# Main.net
KiCad netlist of a schematic drawn in Altium Designer
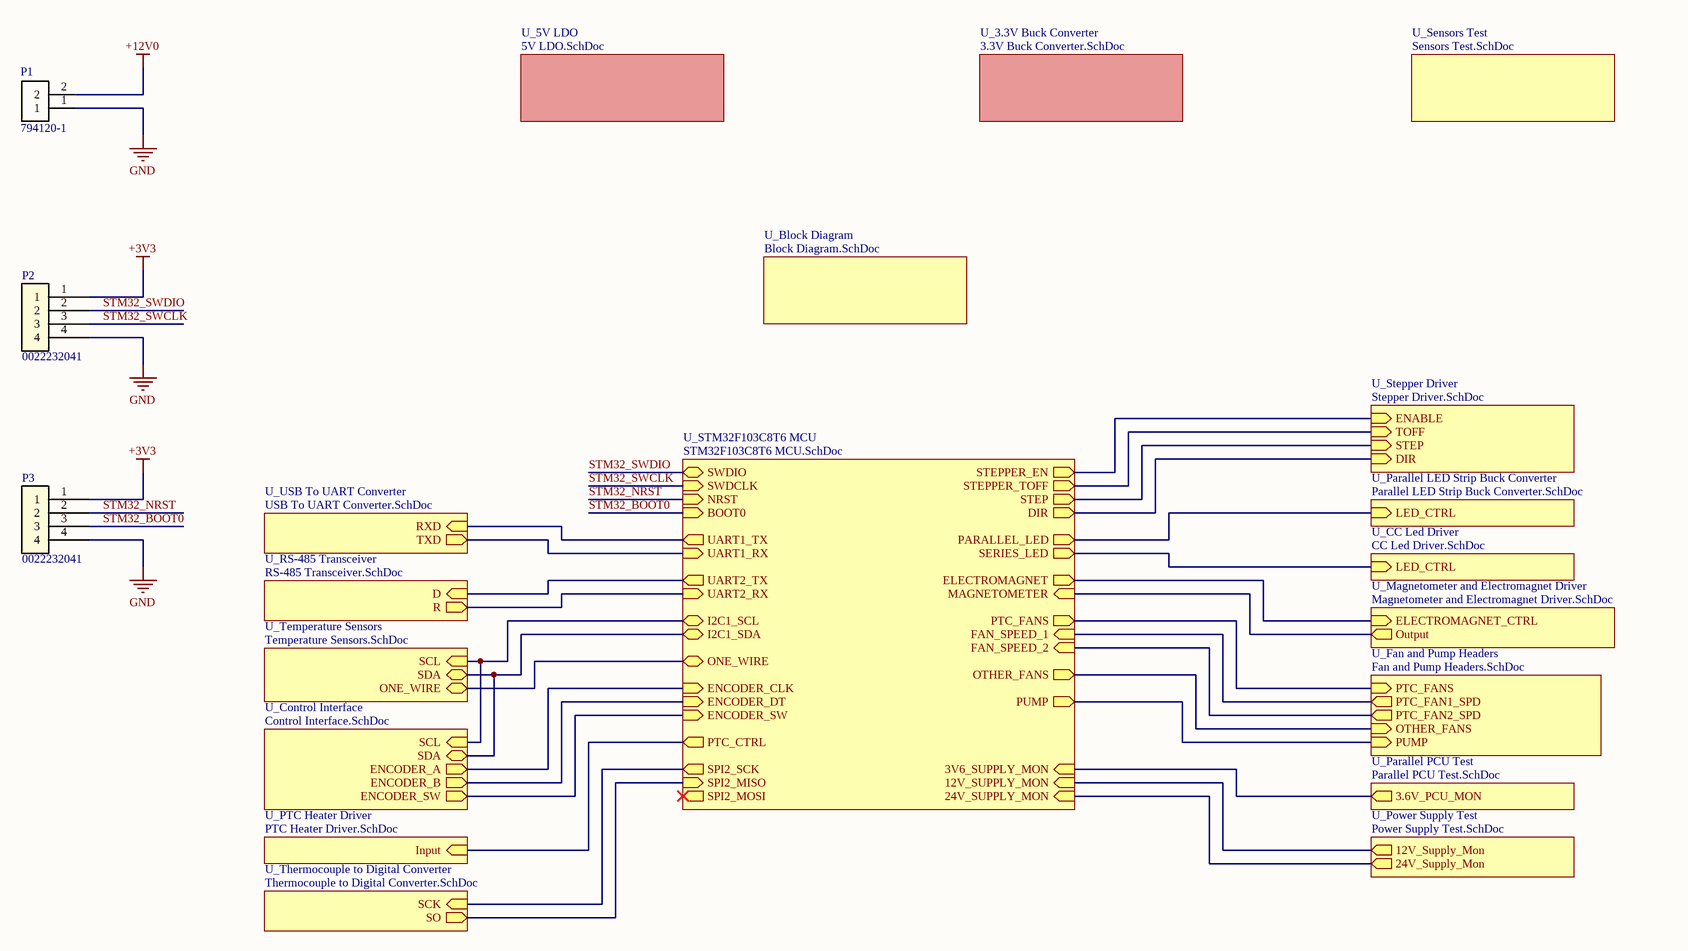
[diagram p0: Main.SchDoc]

(export (version "E")
  (design (tool "Eeschema 10.0.6"))
  (components
    (comp (ref "P1")
      (value "794120-1")
      (footprint "POWER2-5.08 right angle")
      (fields (field (name "MP") "TE Connectivity"))
      (libsource (lib "Connectors") (part "Power2"))
    )
    (comp (ref "P2")
      (value "0022232041")
      (footprint "Signal4")
      (description "SignalConnector, 4 leads")
      (fields (field (name "MF") "Molex"))
      (libsource (lib "Connectors") (part "Signal4"))
    )
    (comp (ref "P3")
      (value "0022232041")
      (footprint "Signal4")
      (description "SignalConnector, 4 leads")
      (fields (field (name "MF") "Molex"))
      (libsource (lib "Connectors") (part "Signal4"))
    )
  )
  (nets
    (net (code "1") (name "+3V3") (class "Default")
      (node (ref "P2") (pin "1") (pinfunction "1_1") (pintype "passive"))
      (node (ref "P3") (pin "1") (pinfunction "1_1") (pintype "passive"))
    )
    (net (code "2") (name "+12V0") (class "Default")
      (node (ref "P1") (pin "2") (pinfunction "2_2") (pintype "passive"))
    )
    (net (code "30") (name "/STM32_BOOT0") (class "Default")
      (node (ref "P3") (pin "3") (pinfunction "3_3") (pintype "passive"))
    )
    (net (code "31") (name "/STM32_NRST") (class "Default")
      (node (ref "P3") (pin "2") (pinfunction "2_2") (pintype "passive"))
    )
    (net (code "32") (name "/STM32_SWCLK") (class "Default")
      (node (ref "P2") (pin "3") (pinfunction "3_3") (pintype "passive"))
    )
    (net (code "33") (name "/STM32_SWDIO") (class "Default")
      (node (ref "P2") (pin "2") (pinfunction "2_2") (pintype "passive"))
    )
    (net (code "37") (name "GND") (class "Default")
      (node (ref "P1") (pin "1") (pinfunction "1_1") (pintype "passive"))
      (node (ref "P2") (pin "4") (pinfunction "4_4") (pintype "passive"))
      (node (ref "P3") (pin "4") (pinfunction "4_4") (pintype "passive"))
    )
  )
)
